# single_button-dual_LED.net
KiCad netlist of a schematic drawn in EAGLE
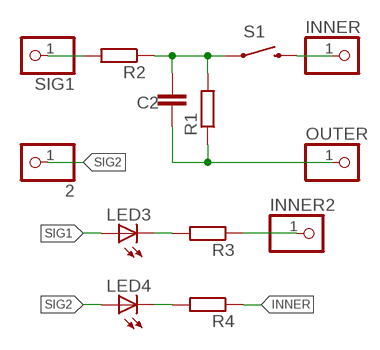
[diagram p0: schematic, sheet 1]

(export (version "E")
  (design (tool "Eeschema 10.0.6"))
  (components
    (comp (ref "2")
      (value "PINHD-1X1CB")
      (footprint "eagle-import:1X01-CLEANBIG")
      (libsource (lib "eagle-import") (part "PINHD-1X1CB"))
    )
    (comp (ref "C2")
      (value "CAPACITOR_NPOL-0805")
      (footprint "eagle-import:C805")
      (libsource (lib "eagle-import") (part "CAPACITOR_NPOL-0805"))
    )
    (comp (ref "INNER")
      (value "PINHD-1X1CB")
      (footprint "eagle-import:1X01-CLEANBIG")
      (libsource (lib "eagle-import") (part "PINHD-1X1CB"))
    )
    (comp (ref "INNER2")
      (value "PINHD-1X1CB")
      (footprint "eagle-import:1X01-CLEANBIG")
      (libsource (lib "eagle-import") (part "PINHD-1X1CB"))
    )
    (comp (ref "LED3")
      (value "LED-0805")
      (footprint "eagle-import:LED-805")
      (libsource (lib "eagle-import") (part "LED-0805"))
    )
    (comp (ref "LED4")
      (value "LED-0805")
      (footprint "eagle-import:LED-805")
      (libsource (lib "eagle-import") (part "LED-0805"))
    )
    (comp (ref "OUTER")
      (value "PINHD-1X1CB")
      (footprint "eagle-import:1X01-CLEANBIG")
      (libsource (lib "eagle-import") (part "PINHD-1X1CB"))
    )
    (comp (ref "R1")
      (value "RESISTORR805-0805")
      (footprint "eagle-import:R805")
      (libsource (lib "eagle-import") (part "RESISTOR-0805R805"))
    )
    (comp (ref "R2")
      (value "RESISTORR805-0805")
      (footprint "eagle-import:R805")
      (libsource (lib "eagle-import") (part "RESISTOR-0805R805"))
    )
    (comp (ref "R3")
      (value "RESISTORR805-0805")
      (footprint "eagle-import:R805")
      (libsource (lib "eagle-import") (part "RESISTOR-0805R805"))
    )
    (comp (ref "R4")
      (value "RESISTORR805-0805")
      (footprint "eagle-import:R805")
      (libsource (lib "eagle-import") (part "RESISTOR-0805R805"))
    )
    (comp (ref "S1")
      (value "SWITCH-MOMENTARY-2PTH")
      (footprint "eagle-import:TACTILE-PTH")
      (libsource (lib "eagle-import") (part "SWITCH-MOMENTARY-2PTH"))
    )
    (comp (ref "SIG1")
      (value "PINHD-1X1CB")
      (footprint "eagle-import:1X01-CLEANBIG")
      (libsource (lib "eagle-import") (part "PINHD-1X1CB"))
    )
  )
  (nets
    (net (code "1") (name "INNER") (class "Default")
      (node (ref "INNER") (pin "1") (pinfunction "1_1") (pintype "passive"))
      (node (ref "R4") (pin "1") (pinfunction "1_1") (pintype "passive"))
      (node (ref "S1") (pin "3") (pinfunction "2_3") (pintype "passive"))
      (node (ref "S1") (pin "4") (pinfunction "2_4") (pintype "passive"))
    )
    (net (code "2") (name "Net-(C2-Pad1)") (class "Default")
      (node (ref "C2") (pin "1") (pinfunction "1_1") (pintype "passive"))
      (node (ref "R1") (pin "2") (pinfunction "2_2") (pintype "passive"))
      (node (ref "R2") (pin "1") (pinfunction "1_1") (pintype "passive"))
      (node (ref "S1") (pin "1") (pinfunction "1_1") (pintype "passive"))
      (node (ref "S1") (pin "2") (pinfunction "1_2") (pintype "passive"))
    )
    (net (code "3") (name "Net-(C2-Pad2)") (class "Default")
      (node (ref "C2") (pin "2") (pinfunction "2_2") (pintype "passive"))
      (node (ref "OUTER") (pin "1") (pinfunction "1_1") (pintype "passive"))
      (node (ref "R1") (pin "1") (pinfunction "1_1") (pintype "passive"))
    )
    (net (code "4") (name "Net-(INNER2-Pad1)") (class "Default")
      (node (ref "INNER2") (pin "1") (pinfunction "1_1") (pintype "passive"))
      (node (ref "R3") (pin "1") (pinfunction "1_1") (pintype "passive"))
    )
    (net (code "5") (name "Net-(LED3-PadC)") (class "Default")
      (node (ref "LED3") (pin "C") (pinfunction "C_C") (pintype "passive"))
      (node (ref "R3") (pin "2") (pinfunction "2_2") (pintype "passive"))
    )
    (net (code "6") (name "Net-(LED4-PadC)") (class "Default")
      (node (ref "LED4") (pin "C") (pinfunction "C_C") (pintype "passive"))
      (node (ref "R4") (pin "2") (pinfunction "2_2") (pintype "passive"))
    )
    (net (code "7") (name "SIG1") (class "Default")
      (node (ref "LED3") (pin "A") (pinfunction "A_A") (pintype "passive"))
      (node (ref "R2") (pin "2") (pinfunction "2_2") (pintype "passive"))
      (node (ref "SIG1") (pin "1") (pinfunction "1_1") (pintype "passive"))
    )
    (net (code "8") (name "SIG2") (class "Default")
      (node (ref "2") (pin "1") (pinfunction "1_1") (pintype "passive"))
      (node (ref "LED4") (pin "A") (pinfunction "A_A") (pintype "passive"))
    )
  )
)
